# Communication.net
KiCad netlist of a schematic drawn in Altium Designer
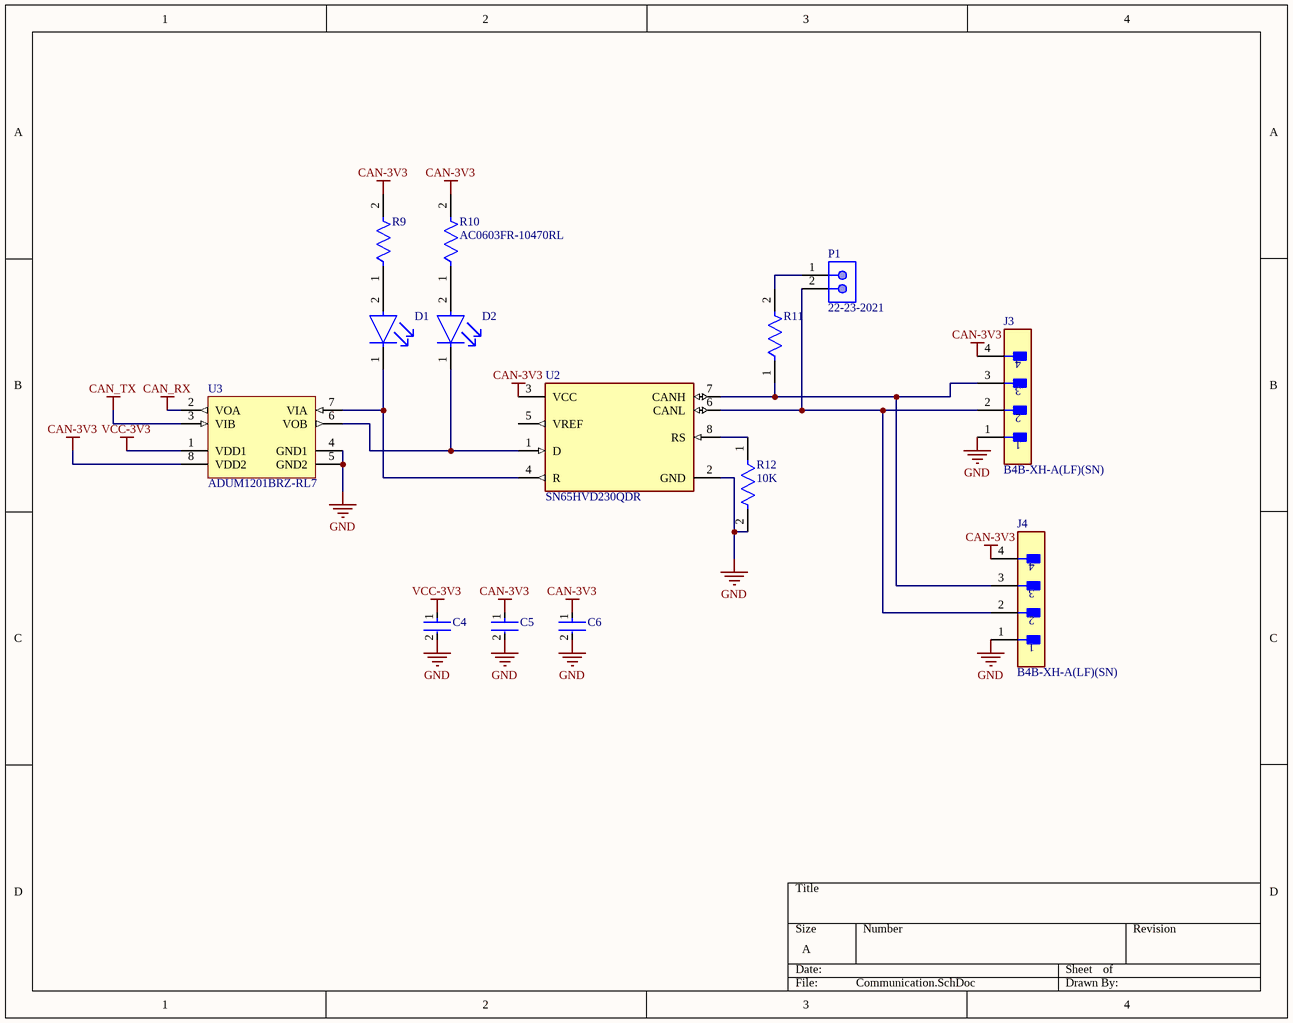
[diagram p0: Communication.SchDoc]

(export (version "E")
  (design (tool "Eeschema 10.0.6"))
  (components
    (comp (ref "C4")
      (value "CC0603KRX7R9BB104")
      (footprint "FP-CC0603-DA-MFG")
      (description "CAP CER 0.1UF 50V X7R 0603")
      (fields (field (name "MANUFACTURER") "YAGEO") (field (name "VOLTAGE") "50 V"))
      (libsource (lib "Altium Content Vault") (part "11868f565c42a9108669ba33697ecf6"))
    )
    (comp (ref "C5")
      (value "CC0603KRX7R9BB104")
      (footprint "FP-CC0603-DA-MFG")
      (description "CAP CER 0.1UF 50V X7R 0603")
      (fields (field (name "MANUFACTURER") "YAGEO") (field (name "VOLTAGE") "50 V"))
      (libsource (lib "Altium Content Vault") (part "11868f565c42a9108669ba33697ecf6"))
    )
    (comp (ref "C6")
      (value "CC0603KRX7R9BB104")
      (footprint "FP-CC0603-DA-MFG")
      (description "CAP CER 0.1UF 50V X7R 0603")
      (fields (field (name "MANUFACTURER") "YAGEO") (field (name "VOLTAGE") "50 V"))
      (libsource (lib "Altium Content Vault") (part "11868f565c42a9108669ba33697ecf6"))
    )
    (comp (ref "D1")
      (value "APHCM2012CGCK-F01")
      (footprint "FP-APHCM2012CGCK-F01-MFG")
      (description "LED GREEN CLEAR CHIP SMD")
      (libsource (lib "Altium Content Vault") (part "8706943c75ba83719d021d2fdc84c58"))
    )
    (comp (ref "D2")
      (value "APHCM2012CGCK-F01")
      (footprint "FP-APHCM2012CGCK-F01-MFG")
      (description "LED GREEN CLEAR CHIP SMD")
      (libsource (lib "Altium Content Vault") (part "8706943c75ba83719d021d2fdc84c58"))
    )
    (comp (ref "J3")
      (value "B4B-XH-A(LF)(SN)")
      (footprint "FP-B4B-XH-A_LF_SN-MFG")
      (description "CONN HEADER VERT 4POS 2.5MM")
      (libsource (lib "Altium Content Vault") (part "299a8cea1bdcbc3624fe62c390fa72c"))
    )
    (comp (ref "J4")
      (value "B4B-XH-A(LF)(SN)")
      (footprint "FP-B4B-XH-A_LF_SN-MFG")
      (description "CONN HEADER VERT 4POS 2.5MM")
      (libsource (lib "Altium Content Vault") (part "299a8cea1bdcbc3624fe62c390fa72c"))
    )
    (comp (ref "P1")
      (value "22-23-2021")
      (footprint "MOLX-22-23-2021_V")
      (libsource (lib "Altium Content Vault") (part "CN-1P-M-R2"))
    )
    (comp (ref "R9")
      (value "AC0603FR-10470RL")
      (footprint "FP-AC0603-IPC_A")
      (description "RES 470Ω 1.00% 0.1W 0603")
      (fields (field (name "TOLERANCE") "1%"))
      (libsource (lib "Altium Content Vault") (part "1029c3af85768c4190bb7ad29bc67b5"))
    )
    (comp (ref "R10")
      (value "AC0603FR-10470RL")
      (footprint "FP-AC0603-IPC_A")
      (description "RES 470Ω 1.00% 0.1W 0603")
      (fields (field (name "TOLERANCE") "1%"))
      (libsource (lib "Altium Content Vault") (part "1029c3af85768c4190bb7ad29bc67b5"))
    )
    (comp (ref "R11")
      (value "RT0603FRE07120RL")
      (footprint "FP-RT0603-MFG")
      (description "RES SMD 120 OHM 1% 1/10W 0603")
      (fields
        (field (name "MANUFACTURER") "Yageo")
        (field (name "OCTOPART") "https://octopart.com/rt0603fre07120rl-yageo-40001924")
      )
      (libsource (lib "Altium Content Vault") (part "1029c3af85768c4190bb7ad29bc67b5"))
    )
    (comp (ref "R12")
      (value "10K")
      (footprint "FP-RC0603-0_55-IPC_C")
      (description "RES 10K OHM 1% 1/10W 0603")
      (fields (field (name "TOLERANCE") "1%"))
      (libsource (lib "Altium Content Vault") (part "1029c3af85768c4190bb7ad29bc67b5"))
    )
    (comp (ref "U2")
      (value "SN65HVD230QDR")
      (footprint "FP-D0008A-IPC_C")
      (description "IC TRANSCEIVER HALF 1/1 8SOIC")
      (libsource (lib "Altium Content Vault") (part "f9a0fcad3056cd5e0648770baa8b623"))
    )
    (comp (ref "U3")
      (value "ADUM1201BRZ-RL7")
      (footprint "ADI-R-8_L")
      (fields (field (name "MANUFACTURER") "Analog Devices"))
      (libsource (lib "Altium Content Vault") (part "ADI-ADUM1201-R-8"))
    )
  )
  (nets
    (net (code "1") (name "CAN-3V3") (class "Default")
      (node (ref "C5") (pin "1") (pinfunction "1_1") (pintype "passive"))
      (node (ref "C6") (pin "1") (pinfunction "1_1") (pintype "passive"))
      (node (ref "J3") (pin "4") (pinfunction "4_4") (pintype "passive"))
      (node (ref "J4") (pin "4") (pinfunction "4_4") (pintype "passive"))
      (node (ref "R10") (pin "2") (pinfunction "2_2") (pintype "passive"))
      (node (ref "R9") (pin "2") (pinfunction "2_2") (pintype "passive"))
      (node (ref "U2") (pin "3") (pinfunction "VCC_3") (pintype "power_in"))
      (node (ref "U3") (pin "8") (pinfunction "VDD2_8") (pintype "power_in"))
    )
    (net (code "2") (name "CAN_RX") (class "Default")
      (node (ref "U3") (pin "2") (pinfunction "VOA_2") (pintype "output"))
    )
    (net (code "3") (name "CAN_TX") (class "Default")
      (node (ref "U3") (pin "3") (pinfunction "VIB_3") (pintype "input"))
    )
    (net (code "4") (name "GND") (class "Default")
      (node (ref "C4") (pin "2") (pinfunction "2_2") (pintype "passive"))
      (node (ref "C5") (pin "2") (pinfunction "2_2") (pintype "passive"))
      (node (ref "C6") (pin "2") (pinfunction "2_2") (pintype "passive"))
      (node (ref "J3") (pin "1") (pinfunction "1_1") (pintype "passive"))
      (node (ref "J4") (pin "1") (pinfunction "1_1") (pintype "passive"))
      (node (ref "R12") (pin "2") (pinfunction "2_2") (pintype "passive"))
      (node (ref "U2") (pin "2") (pinfunction "GND_2") (pintype "power_in"))
      (node (ref "U3") (pin "4") (pinfunction "GND1_4") (pintype "power_in"))
      (node (ref "U3") (pin "5") (pinfunction "GND2_5") (pintype "power_in"))
    )
    (net (code "5") (name "Net-(D1-A)") (class "Default")
      (node (ref "D1") (pin "2") (pinfunction "A_2") (pintype "passive"))
      (node (ref "R9") (pin "1") (pinfunction "1_1") (pintype "passive"))
    )
    (net (code "6") (name "Net-(D1-C)") (class "Default")
      (node (ref "D1") (pin "1") (pinfunction "C_1") (pintype "passive"))
      (node (ref "U2") (pin "4") (pinfunction "R_4") (pintype "output"))
      (node (ref "U3") (pin "7") (pinfunction "VIA_7") (pintype "input"))
    )
    (net (code "7") (name "Net-(D2-A)") (class "Default")
      (node (ref "D2") (pin "2") (pinfunction "A_2") (pintype "passive"))
      (node (ref "R10") (pin "1") (pinfunction "1_1") (pintype "passive"))
    )
    (net (code "8") (name "Net-(D2-C)") (class "Default")
      (node (ref "D2") (pin "1") (pinfunction "C_1") (pintype "passive"))
      (node (ref "U2") (pin "1") (pinfunction "D_1") (pintype "input"))
      (node (ref "U3") (pin "6") (pinfunction "VOB_6") (pintype "output"))
    )
    (net (code "9") (name "Net-(P1-Pad1)") (class "Default")
      (node (ref "P1") (pin "1") (pinfunction "1_1") (pintype "passive"))
      (node (ref "R11") (pin "2") (pinfunction "2_2") (pintype "passive"))
    )
    (net (code "10") (name "Net-(U2-CANH)") (class "Default")
      (node (ref "J3") (pin "3") (pinfunction "3_3") (pintype "passive"))
      (node (ref "J4") (pin "3") (pinfunction "3_3") (pintype "passive"))
      (node (ref "R11") (pin "1") (pinfunction "1_1") (pintype "passive"))
      (node (ref "U2") (pin "7") (pinfunction "CANH_7") (pintype "bidirectional"))
    )
    (net (code "11") (name "Net-(U2-CANL)") (class "Default")
      (node (ref "J3") (pin "2") (pinfunction "2_2") (pintype "passive"))
      (node (ref "J4") (pin "2") (pinfunction "2_2") (pintype "passive"))
      (node (ref "P1") (pin "2") (pinfunction "2_2") (pintype "passive"))
      (node (ref "U2") (pin "6") (pinfunction "CANL_6") (pintype "bidirectional"))
    )
    (net (code "12") (name "Net-(U2-RS)") (class "Default")
      (node (ref "R12") (pin "1") (pinfunction "1_1") (pintype "passive"))
      (node (ref "U2") (pin "8") (pinfunction "RS_8") (pintype "input"))
    )
    (net (code "13") (name "VCC-3V3") (class "Default")
      (node (ref "C4") (pin "1") (pinfunction "1_1") (pintype "passive"))
      (node (ref "U3") (pin "1") (pinfunction "VDD1_1") (pintype "power_in"))
    )
    (net (code "14") (name "unconnected-(U2-VREF-Pad5)") (class "Default")
      (node (ref "U2") (pin "5") (pinfunction "VREF_5") (pintype "output"))
    )
  )
)
